# POWER_2.net
KiCad netlist of a schematic drawn in Altium Designer
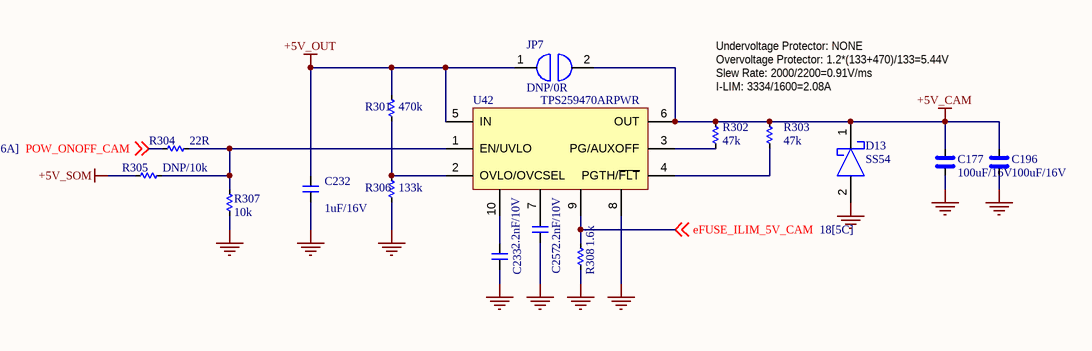
[diagram p0: POWER_2.SchDoc]

(export (version "E")
  (design (tool "Eeschema 10.0.6"))
  (components
    (comp (ref "C177")
      (value "100uF/16V")
      (footprint "CAP_C_3225X80")
      (description "CAP CHIP High Value")
      (libsource (lib "LABLIB") (part "_CAP_C_High_2"))
    )
    (comp (ref "C196")
      (value "100uF/16V")
      (footprint "CAP_C_3225X80")
      (description "CAP CHIP High Value")
      (libsource (lib "LABLIB") (part "_CAP_C_High_2"))
    )
    (comp (ref "C232")
      (value "1uF/16V")
      (footprint "CAP_C_1005X60")
      (description "CAP CHIP")
      (libsource (lib "LABLIB") (part "_CAP_C_2"))
    )
    (comp (ref "C233")
      (value "2.2nF/10V")
      (footprint "CAP_C_1005X60")
      (description "CAP CHIP")
      (libsource (lib "LABLIB") (part "_CAP_C_2"))
    )
    (comp (ref "C257")
      (value "2.2nF/10V")
      (footprint "CAP_C_1005X60")
      (description "CAP CHIP")
      (libsource (lib "LABLIB") (part "_CAP_C_2"))
    )
    (comp (ref "D13")
      (value "SS54")
      (footprint "DO-214AC_SMA")
      (description "DIODE SCHOTTKY 60V 3A DO214AA")
      (libsource (lib "EXP_HW_V3") (part "SS54"))
    )
    (comp (ref "JP7") (value "DNP/0R") (footprint "RES_C_1608X60") (libsource (lib "EXP_V1") (part "JUMPER")))
    (comp (ref "R301")
      (value "470k")
      (footprint "RES_C_1005X40")
      (description "RES")
      (libsource (lib "LABLIB") (part "_RES_B_2"))
    )
    (comp (ref "R302")
      (value "47k")
      (footprint "RES_C_1005X40")
      (description "RES")
      (libsource (lib "LABLIB") (part "_RES_B_2"))
    )
    (comp (ref "R303")
      (value "47k")
      (footprint "RES_C_1005X40")
      (description "RES")
      (libsource (lib "LABLIB") (part "_RES_B_2"))
    )
    (comp (ref "R304")
      (value "22R")
      (footprint "RES_C_1005X40")
      (description "RES")
      (libsource (lib "LABLIB") (part "_RES_B_2"))
    )
    (comp (ref "R305")
      (value "DNP/10k")
      (footprint "RES_C_1005X40")
      (description "RES")
      (libsource (lib "LABLIB") (part "_RES_B_2"))
    )
    (comp (ref "R306")
      (value "133k")
      (footprint "RES_C_1005X40")
      (description "RES")
      (libsource (lib "LABLIB") (part "_RES_B_2"))
    )
    (comp (ref "R307")
      (value "10k")
      (footprint "RES_C_1005X40")
      (description "RES")
      (libsource (lib "LABLIB") (part "_RES_B_2"))
    )
    (comp (ref "R308")
      (value "1.6k")
      (footprint "RES_C_1005X40")
      (description "RES")
      (libsource (lib "LABLIB") (part "_RES_B_2"))
    )
    (comp (ref "U42")
      (value "TPS259470ARPWR")
      (footprint "VQFN-HR-10")
      (libsource (lib "EXP_HW_V3") (part "TPS259470ARPWR"))
    )
  )
  (nets
    (net (code "1") (name "+5V_CAM") (class "Default")
      (node (ref "C177") (pin "2") (pinfunction "2_2") (pintype "passive"))
      (node (ref "C196") (pin "2") (pinfunction "2_2") (pintype "passive"))
      (node (ref "D13") (pin "1") (pinfunction "1_1") (pintype "passive"))
      (node (ref "JP7") (pin "2") (pinfunction "2_2") (pintype "passive"))
      (node (ref "R302") (pin "2") (pinfunction "2_2") (pintype "passive"))
      (node (ref "R303") (pin "2") (pinfunction "2_2") (pintype "passive"))
      (node (ref "U42") (pin "6") (pinfunction "OUT_6") (pintype "passive"))
    )
    (net (code "2") (name "+5V_OUT") (class "Default")
      (node (ref "C232") (pin "2") (pinfunction "2_2") (pintype "passive"))
      (node (ref "JP7") (pin "1") (pinfunction "1_1") (pintype "passive"))
      (node (ref "R301") (pin "2") (pinfunction "2_2") (pintype "passive"))
      (node (ref "U42") (pin "5") (pinfunction "IN_5") (pintype "passive"))
    )
    (net (code "3") (name "+5V_SOM") (class "Default")
      (node (ref "R305") (pin "2") (pinfunction "2_2") (pintype "passive"))
    )
    (net (code "4") (name "GND") (class "Default")
      (node (ref "C177") (pin "1") (pinfunction "1_1") (pintype "passive"))
      (node (ref "C196") (pin "1") (pinfunction "1_1") (pintype "passive"))
      (node (ref "C232") (pin "1") (pinfunction "1_1") (pintype "passive"))
      (node (ref "C233") (pin "1") (pinfunction "1_1") (pintype "passive"))
      (node (ref "C257") (pin "1") (pinfunction "1_1") (pintype "passive"))
      (node (ref "D13") (pin "2") (pinfunction "2_2") (pintype "passive"))
      (node (ref "R306") (pin "1") (pinfunction "1_1") (pintype "passive"))
      (node (ref "R307") (pin "2") (pinfunction "2_2") (pintype "passive"))
      (node (ref "R308") (pin "1") (pinfunction "1_1") (pintype "passive"))
      (node (ref "U42") (pin "8") (pinfunction "8_8") (pintype "passive"))
    )
    (net (code "5") (name "Net-(C233-Pad2)") (class "Default")
      (node (ref "C233") (pin "2") (pinfunction "2_2") (pintype "passive"))
      (node (ref "U42") (pin "10") (pinfunction "10_10") (pintype "passive"))
    )
    (net (code "6") (name "Net-(C257-Pad2)") (class "Default")
      (node (ref "C257") (pin "2") (pinfunction "2_2") (pintype "passive"))
      (node (ref "U42") (pin "7") (pinfunction "7_7") (pintype "passive"))
    )
    (net (code "7") (name "Net-(U42-EN{slash}UVLO)") (class "Default")
      (node (ref "R304") (pin "1") (pinfunction "1_1") (pintype "passive"))
      (node (ref "R305") (pin "1") (pinfunction "1_1") (pintype "passive"))
      (node (ref "R307") (pin "1") (pinfunction "1_1") (pintype "passive"))
      (node (ref "U42") (pin "1") (pinfunction "EN/UVLO_1") (pintype "passive"))
    )
    (net (code "8") (name "Net-(U42-OVLO{slash}OVCSEL)") (class "Default")
      (node (ref "R301") (pin "1") (pinfunction "1_1") (pintype "passive"))
      (node (ref "R306") (pin "2") (pinfunction "2_2") (pintype "passive"))
      (node (ref "U42") (pin "2") (pinfunction "OVLO/OVCSEL_2") (pintype "passive"))
    )
    (net (code "9") (name "Net-(U42-PGTH{slash}~{FLT})") (class "Default")
      (node (ref "R303") (pin "1") (pinfunction "1_1") (pintype "passive"))
      (node (ref "U42") (pin "4") (pinfunction "PGTH/~{FLT}_4") (pintype "passive"))
    )
    (net (code "10") (name "Net-(U42-PG{slash}AUXOFF)") (class "Default")
      (node (ref "R302") (pin "1") (pinfunction "1_1") (pintype "passive"))
      (node (ref "U42") (pin "3") (pinfunction "PG/AUXOFF_3") (pintype "passive"))
    )
    (net (code "11") (name "POW_ONOFF_CAM") (class "Default")
      (node (ref "R304") (pin "2") (pinfunction "2_2") (pintype "passive"))
    )
    (net (code "12") (name "eFUSE_ILIM_5V_CAM") (class "Default")
      (node (ref "R308") (pin "2") (pinfunction "2_2") (pintype "passive"))
      (node (ref "U42") (pin "9") (pinfunction "9_9") (pintype "passive"))
    )
  )
)
